# TMS320F28379D.net
KiCad netlist of a schematic drawn in Altium Designer
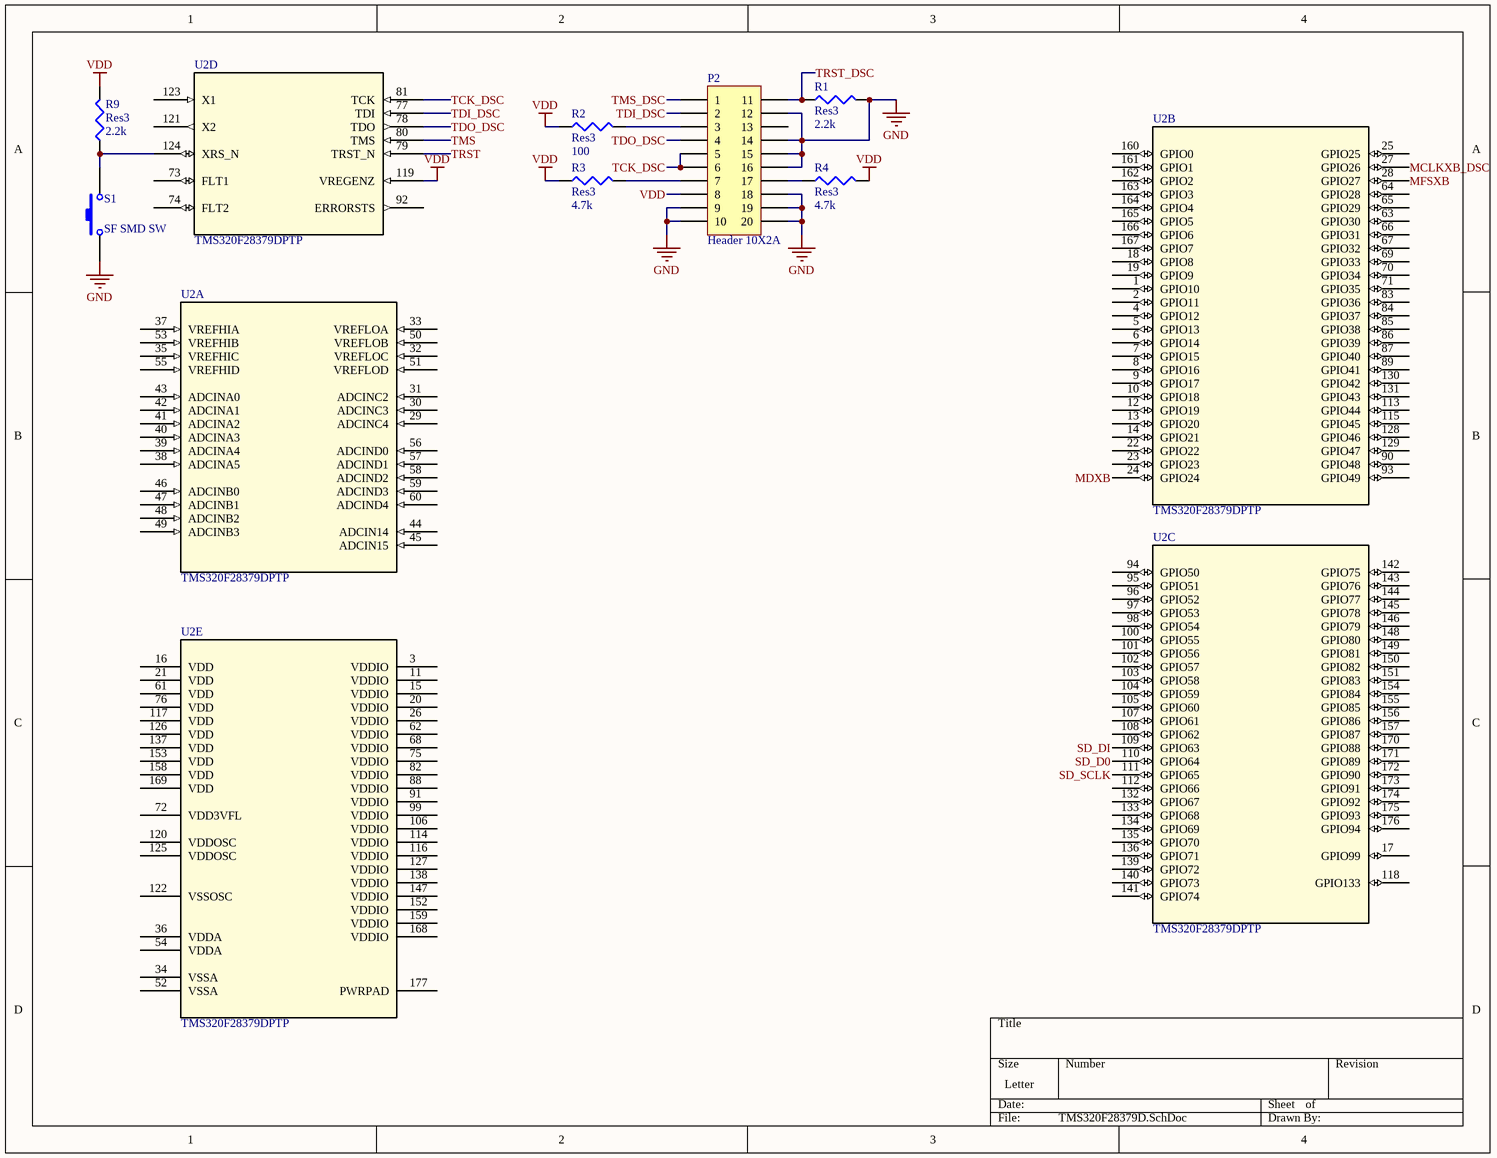
[diagram p0: TMS320F28379D.SchDoc]

(export (version "E")
  (design (tool "Eeschema 10.0.6"))
  (components
    (comp (ref "P2")
      (value "Header 10X2A")
      (footprint "HDR2X10_CEN")
      (description "Header, 10-Pin, Dual row")
      (fields (field (name "PUBLISHER") "Altium Limited"))
      (libsource (lib "Miscellaneous Connectors") (part "Header 10X2A"))
    )
    (comp (ref "R1")
      (value "Res3")
      (footprint "J1-0603")
      (description "Resistor")
      (fields (field (name "ALTIUM_VALUE") "2.2k") (field (name "PUBLISHER") "Altium Limited"))
      (libsource (lib "Miscellaneous Devices") (part "Res3"))
    )
    (comp (ref "R2")
      (value "Res3")
      (footprint "J1-0603")
      (description "Resistor")
      (fields (field (name "ALTIUM_VALUE") "100") (field (name "PUBLISHER") "Altium Limited"))
      (libsource (lib "Miscellaneous Devices") (part "Res3"))
    )
    (comp (ref "R3")
      (value "Res3")
      (footprint "J1-0603")
      (description "Resistor")
      (fields (field (name "ALTIUM_VALUE") "4.7k") (field (name "PUBLISHER") "Altium Limited"))
      (libsource (lib "Miscellaneous Devices") (part "Res3"))
    )
    (comp (ref "R4")
      (value "Res3")
      (footprint "J1-0603")
      (description "Resistor")
      (fields (field (name "ALTIUM_VALUE") "4.7k") (field (name "PUBLISHER") "Altium Limited"))
      (libsource (lib "Miscellaneous Devices") (part "Res3"))
    )
    (comp (ref "R9")
      (value "Res3")
      (footprint "J1-0603")
      (description "Resistor")
      (fields (field (name "ALTIUM_VALUE") "2.2k") (field (name "PUBLISHER") "Altium Limited"))
      (libsource (lib "Miscellaneous Devices") (part "Res3"))
    )
    (comp (ref "S1")
      (value "SF SMD SW")
      (footprint "SW_SMD")
      (description "DIGIKEY SW400-ND")
      (fields (field (name "PUBLISHER") "Altium Limited"))
      (libsource (lib "ECE LIB new") (part "SW-PB_1"))
    )
    (comp (ref "U2")
      (value "TMS320F28379DPTP")
      (footprint "PTP0176F_N")
      (description "Imported")
      (fields
        (field (name "PARTNUMBER") "TMS320F28379DPTPS")
        (field (name "MANUFACTURER") "Texas Instruments")
      )
      (libsource (lib "TMS320F28379DPTP") (part "TMS320F28379DPTP"))
    )
  )
  (nets
    (net (code "1") (name "/MCLKXB_DSC") (class "Default")
      (node (ref "U2") (pin "27") (pinfunction "GPIO26_27") (pintype "bidirectional"))
    )
    (net (code "2") (name "/MDXB") (class "Default")
      (node (ref "U2") (pin "24") (pinfunction "GPIO24_24") (pintype "bidirectional"))
    )
    (net (code "3") (name "/MFSXB") (class "Default")
      (node (ref "U2") (pin "28") (pinfunction "GPIO27_28") (pintype "bidirectional"))
    )
    (net (code "4") (name "/SD_D0") (class "Default")
      (node (ref "U2") (pin "110") (pinfunction "GPIO64_110") (pintype "bidirectional"))
    )
    (net (code "5") (name "/SD_DI") (class "Default")
      (node (ref "U2") (pin "109") (pinfunction "GPIO63_109") (pintype "bidirectional"))
    )
    (net (code "6") (name "/SD_SCLK") (class "Default")
      (node (ref "U2") (pin "111") (pinfunction "GPIO65_111") (pintype "bidirectional"))
    )
    (net (code "7") (name "/TCK_DSC") (class "Default")
      (node (ref "P2") (pin "5") (pinfunction "5_5") (pintype "passive"))
      (node (ref "P2") (pin "6") (pinfunction "6_6") (pintype "passive"))
      (node (ref "U2") (pin "81") (pinfunction "TCK_81") (pintype "input"))
    )
    (net (code "8") (name "/TDI_DSC") (class "Default")
      (node (ref "P2") (pin "2") (pinfunction "2_2") (pintype "passive"))
      (node (ref "U2") (pin "77") (pinfunction "TDI_77") (pintype "input"))
    )
    (net (code "9") (name "/TDO_DSC") (class "Default")
      (node (ref "P2") (pin "4") (pinfunction "4_4") (pintype "passive"))
      (node (ref "U2") (pin "78") (pinfunction "TDO_78") (pintype "output"))
    )
    (net (code "10") (name "/TMS") (class "Default")
      (node (ref "U2") (pin "80") (pinfunction "TMS_80") (pintype "input"))
    )
    (net (code "11") (name "/TMS_DSC") (class "Default")
      (node (ref "P2") (pin "1") (pinfunction "1_1") (pintype "passive"))
    )
    (net (code "12") (name "/TRST") (class "Default")
      (node (ref "U2") (pin "79") (pinfunction "TRST_N_79") (pintype "input"))
    )
    (net (code "13") (name "/TRST_DSC") (class "Default")
      (node (ref "P2") (pin "11") (pinfunction "11_11") (pintype "passive"))
      (node (ref "R1") (pin "1") (pinfunction "1_1") (pintype "passive"))
    )
    (net (code "14") (name "GND") (class "Default")
      (node (ref "P2") (pin "10") (pinfunction "10_10") (pintype "passive"))
      (node (ref "P2") (pin "12") (pinfunction "12_12") (pintype "passive"))
      (node (ref "P2") (pin "14") (pinfunction "14_14") (pintype "passive"))
      (node (ref "P2") (pin "15") (pinfunction "15_15") (pintype "passive"))
      (node (ref "P2") (pin "16") (pinfunction "16_16") (pintype "passive"))
      (node (ref "P2") (pin "18") (pinfunction "18_18") (pintype "passive"))
      (node (ref "P2") (pin "19") (pinfunction "19_19") (pintype "passive"))
      (node (ref "P2") (pin "20") (pinfunction "20_20") (pintype "passive"))
      (node (ref "P2") (pin "9") (pinfunction "9_9") (pintype "passive"))
      (node (ref "R1") (pin "2") (pinfunction "2_2") (pintype "passive"))
      (node (ref "S1") (pin "1") (pinfunction "1_1") (pintype "passive"))
    )
    (net (code "15") (name "Net-(P2-Pad3)") (class "Default")
      (node (ref "P2") (pin "3") (pinfunction "3_3") (pintype "passive"))
      (node (ref "R2") (pin "2") (pinfunction "2_2") (pintype "passive"))
    )
    (net (code "16") (name "Net-(P2-Pad7)") (class "Default")
      (node (ref "P2") (pin "7") (pinfunction "7_7") (pintype "passive"))
      (node (ref "R3") (pin "2") (pinfunction "2_2") (pintype "passive"))
    )
    (net (code "17") (name "Net-(P2-Pad17)") (class "Default")
      (node (ref "P2") (pin "17") (pinfunction "17_17") (pintype "passive"))
      (node (ref "R4") (pin "1") (pinfunction "1_1") (pintype "passive"))
    )
    (net (code "18") (name "Net-(U2D-XRS_N)") (class "Default")
      (node (ref "R9") (pin "1") (pinfunction "1_1") (pintype "passive"))
      (node (ref "S1") (pin "2") (pinfunction "2_2") (pintype "passive"))
      (node (ref "U2") (pin "124") (pinfunction "XRS_N_124") (pintype "bidirectional"))
    )
    (net (code "19") (name "VDD") (class "Default")
      (node (ref "P2") (pin "8") (pinfunction "8_8") (pintype "passive"))
      (node (ref "R2") (pin "1") (pinfunction "1_1") (pintype "passive"))
      (node (ref "R3") (pin "1") (pinfunction "1_1") (pintype "passive"))
      (node (ref "R4") (pin "2") (pinfunction "2_2") (pintype "passive"))
      (node (ref "R9") (pin "2") (pinfunction "2_2") (pintype "passive"))
      (node (ref "U2") (pin "119") (pinfunction "VREGENZ_119") (pintype "input"))
    )
    (net (code "20") (name "unconnected-(P2-Pad13)") (class "Default")
      (node (ref "P2") (pin "13") (pinfunction "13_13") (pintype "passive"))
    )
    (net (code "21") (name "unconnected-(U2A-ADCIN14-Pad44)") (class "Default")
      (node (ref "U2") (pin "44") (pinfunction "ADCIN14_44") (pintype "input"))
    )
    (net (code "22") (name "unconnected-(U2A-ADCIN15-Pad45)") (class "Default")
      (node (ref "U2") (pin "45") (pinfunction "ADCIN15_45") (pintype "input"))
    )
    (net (code "23") (name "unconnected-(U2A-ADCINA0-Pad43)") (class "Default")
      (node (ref "U2") (pin "43") (pinfunction "ADCINA0_43") (pintype "input"))
    )
    (net (code "24") (name "unconnected-(U2A-ADCINA1-Pad42)") (class "Default")
      (node (ref "U2") (pin "42") (pinfunction "ADCINA1_42") (pintype "input"))
    )
    (net (code "25") (name "unconnected-(U2A-ADCINA2-Pad41)") (class "Default")
      (node (ref "U2") (pin "41") (pinfunction "ADCINA2_41") (pintype "input"))
    )
    (net (code "26") (name "unconnected-(U2A-ADCINA3-Pad40)") (class "Default")
      (node (ref "U2") (pin "40") (pinfunction "ADCINA3_40") (pintype "input"))
    )
    (net (code "27") (name "unconnected-(U2A-ADCINA4-Pad39)") (class "Default")
      (node (ref "U2") (pin "39") (pinfunction "ADCINA4_39") (pintype "input"))
    )
    (net (code "28") (name "unconnected-(U2A-ADCINA5-Pad38)") (class "Default")
      (node (ref "U2") (pin "38") (pinfunction "ADCINA5_38") (pintype "input"))
    )
    (net (code "29") (name "unconnected-(U2A-ADCINB0-Pad46)") (class "Default")
      (node (ref "U2") (pin "46") (pinfunction "ADCINB0_46") (pintype "input"))
    )
    (net (code "30") (name "unconnected-(U2A-ADCINB1-Pad47)") (class "Default")
      (node (ref "U2") (pin "47") (pinfunction "ADCINB1_47") (pintype "input"))
    )
    (net (code "31") (name "unconnected-(U2A-ADCINB2-Pad48)") (class "Default")
      (node (ref "U2") (pin "48") (pinfunction "ADCINB2_48") (pintype "input"))
    )
    (net (code "32") (name "unconnected-(U2A-ADCINB3-Pad49)") (class "Default")
      (node (ref "U2") (pin "49") (pinfunction "ADCINB3_49") (pintype "input"))
    )
    (net (code "33") (name "unconnected-(U2A-ADCINC2-Pad31)") (class "Default")
      (node (ref "U2") (pin "31") (pinfunction "ADCINC2_31") (pintype "input"))
    )
    (net (code "34") (name "unconnected-(U2A-ADCINC3-Pad30)") (class "Default")
      (node (ref "U2") (pin "30") (pinfunction "ADCINC3_30") (pintype "input"))
    )
    (net (code "35") (name "unconnected-(U2A-ADCINC4-Pad29)") (class "Default")
      (node (ref "U2") (pin "29") (pinfunction "ADCINC4_29") (pintype "input"))
    )
    (net (code "36") (name "unconnected-(U2A-ADCIND0-Pad56)") (class "Default")
      (node (ref "U2") (pin "56") (pinfunction "ADCIND0_56") (pintype "input"))
    )
    (net (code "37") (name "unconnected-(U2A-ADCIND1-Pad57)") (class "Default")
      (node (ref "U2") (pin "57") (pinfunction "ADCIND1_57") (pintype "input"))
    )
    (net (code "38") (name "unconnected-(U2A-ADCIND2-Pad58)") (class "Default")
      (node (ref "U2") (pin "58") (pinfunction "ADCIND2_58") (pintype "input"))
    )
    (net (code "39") (name "unconnected-(U2A-ADCIND3-Pad59)") (class "Default")
      (node (ref "U2") (pin "59") (pinfunction "ADCIND3_59") (pintype "input"))
    )
    (net (code "40") (name "unconnected-(U2A-ADCIND4-Pad60)") (class "Default")
      (node (ref "U2") (pin "60") (pinfunction "ADCIND4_60") (pintype "input"))
    )
    (net (code "41") (name "unconnected-(U2A-VREFHIA-Pad37)") (class "Default")
      (node (ref "U2") (pin "37") (pinfunction "VREFHIA_37") (pintype "input"))
    )
    (net (code "42") (name "unconnected-(U2A-VREFHIB-Pad53)") (class "Default")
      (node (ref "U2") (pin "53") (pinfunction "VREFHIB_53") (pintype "input"))
    )
    (net (code "43") (name "unconnected-(U2A-VREFHIC-Pad35)") (class "Default")
      (node (ref "U2") (pin "35") (pinfunction "VREFHIC_35") (pintype "input"))
    )
    (net (code "44") (name "unconnected-(U2A-VREFHID-Pad55)") (class "Default")
      (node (ref "U2") (pin "55") (pinfunction "VREFHID_55") (pintype "input"))
    )
    (net (code "45") (name "unconnected-(U2A-VREFLOA-Pad33)") (class "Default")
      (node (ref "U2") (pin "33") (pinfunction "VREFLOA_33") (pintype "input"))
    )
    (net (code "46") (name "unconnected-(U2A-VREFLOB-Pad50)") (class "Default")
      (node (ref "U2") (pin "50") (pinfunction "VREFLOB_50") (pintype "input"))
    )
    (net (code "47") (name "unconnected-(U2A-VREFLOC-Pad32)") (class "Default")
      (node (ref "U2") (pin "32") (pinfunction "VREFLOC_32") (pintype "input"))
    )
    (net (code "48") (name "unconnected-(U2A-VREFLOD-Pad51)") (class "Default")
      (node (ref "U2") (pin "51") (pinfunction "VREFLOD_51") (pintype "input"))
    )
    (net (code "49") (name "unconnected-(U2B-GPIO0-Pad160)") (class "Default")
      (node (ref "U2") (pin "160") (pinfunction "GPIO0_160") (pintype "bidirectional"))
    )
    (net (code "50") (name "unconnected-(U2B-GPIO1-Pad161)") (class "Default")
      (node (ref "U2") (pin "161") (pinfunction "GPIO1_161") (pintype "bidirectional"))
    )
    (net (code "51") (name "unconnected-(U2B-GPIO2-Pad162)") (class "Default")
      (node (ref "U2") (pin "162") (pinfunction "GPIO2_162") (pintype "bidirectional"))
    )
    (net (code "52") (name "unconnected-(U2B-GPIO3-Pad163)") (class "Default")
      (node (ref "U2") (pin "163") (pinfunction "GPIO3_163") (pintype "bidirectional"))
    )
    (net (code "53") (name "unconnected-(U2B-GPIO4-Pad164)") (class "Default")
      (node (ref "U2") (pin "164") (pinfunction "GPIO4_164") (pintype "bidirectional"))
    )
    (net (code "54") (name "unconnected-(U2B-GPIO5-Pad165)") (class "Default")
      (node (ref "U2") (pin "165") (pinfunction "GPIO5_165") (pintype "bidirectional"))
    )
    (net (code "55") (name "unconnected-(U2B-GPIO6-Pad166)") (class "Default")
      (node (ref "U2") (pin "166") (pinfunction "GPIO6_166") (pintype "bidirectional"))
    )
    (net (code "56") (name "unconnected-(U2B-GPIO7-Pad167)") (class "Default")
      (node (ref "U2") (pin "167") (pinfunction "GPIO7_167") (pintype "bidirectional"))
    )
    (net (code "57") (name "unconnected-(U2B-GPIO8-Pad18)") (class "Default")
      (node (ref "U2") (pin "18") (pinfunction "GPIO8_18") (pintype "bidirectional"))
    )
    (net (code "58") (name "unconnected-(U2B-GPIO9-Pad19)") (class "Default")
      (node (ref "U2") (pin "19") (pinfunction "GPIO9_19") (pintype "bidirectional"))
    )
    (net (code "59") (name "unconnected-(U2B-GPIO10-Pad1)") (class "Default")
      (node (ref "U2") (pin "1") (pinfunction "GPIO10_1") (pintype "bidirectional"))
    )
    (net (code "60") (name "unconnected-(U2B-GPIO11-Pad2)") (class "Default")
      (node (ref "U2") (pin "2") (pinfunction "GPIO11_2") (pintype "bidirectional"))
    )
    (net (code "61") (name "unconnected-(U2B-GPIO12-Pad4)") (class "Default")
      (node (ref "U2") (pin "4") (pinfunction "GPIO12_4") (pintype "bidirectional"))
    )
    (net (code "62") (name "unconnected-(U2B-GPIO13-Pad5)") (class "Default")
      (node (ref "U2") (pin "5") (pinfunction "GPIO13_5") (pintype "bidirectional"))
    )
    (net (code "63") (name "unconnected-(U2B-GPIO14-Pad6)") (class "Default")
      (node (ref "U2") (pin "6") (pinfunction "GPIO14_6") (pintype "bidirectional"))
    )
    (net (code "64") (name "unconnected-(U2B-GPIO15-Pad7)") (class "Default")
      (node (ref "U2") (pin "7") (pinfunction "GPIO15_7") (pintype "bidirectional"))
    )
    (net (code "65") (name "unconnected-(U2B-GPIO16-Pad8)") (class "Default")
      (node (ref "U2") (pin "8") (pinfunction "GPIO16_8") (pintype "bidirectional"))
    )
    (net (code "66") (name "unconnected-(U2B-GPIO17-Pad9)") (class "Default")
      (node (ref "U2") (pin "9") (pinfunction "GPIO17_9") (pintype "bidirectional"))
    )
    (net (code "67") (name "unconnected-(U2B-GPIO18-Pad10)") (class "Default")
      (node (ref "U2") (pin "10") (pinfunction "GPIO18_10") (pintype "bidirectional"))
    )
    (net (code "68") (name "unconnected-(U2B-GPIO19-Pad12)") (class "Default")
      (node (ref "U2") (pin "12") (pinfunction "GPIO19_12") (pintype "bidirectional"))
    )
    (net (code "69") (name "unconnected-(U2B-GPIO20-Pad13)") (class "Default")
      (node (ref "U2") (pin "13") (pinfunction "GPIO20_13") (pintype "bidirectional"))
    )
    (net (code "70") (name "unconnected-(U2B-GPIO21-Pad14)") (class "Default")
      (node (ref "U2") (pin "14") (pinfunction "GPIO21_14") (pintype "bidirectional"))
    )
    (net (code "71") (name "unconnected-(U2B-GPIO22-Pad22)") (class "Default")
      (node (ref "U2") (pin "22") (pinfunction "GPIO22_22") (pintype "bidirectional"))
    )
    (net (code "72") (name "unconnected-(U2B-GPIO23-Pad23)") (class "Default")
      (node (ref "U2") (pin "23") (pinfunction "GPIO23_23") (pintype "bidirectional"))
    )
    (net (code "73") (name "unconnected-(U2B-GPIO25-Pad25)") (class "Default")
      (node (ref "U2") (pin "25") (pinfunction "GPIO25_25") (pintype "bidirectional"))
    )
    (net (code "74") (name "unconnected-(U2B-GPIO28-Pad64)") (class "Default")
      (node (ref "U2") (pin "64") (pinfunction "GPIO28_64") (pintype "bidirectional"))
    )
    (net (code "75") (name "unconnected-(U2B-GPIO29-Pad65)") (class "Default")
      (node (ref "U2") (pin "65") (pinfunction "GPIO29_65") (pintype "bidirectional"))
    )
    (net (code "76") (name "unconnected-(U2B-GPIO30-Pad63)") (class "Default")
      (node (ref "U2") (pin "63") (pinfunction "GPIO30_63") (pintype "bidirectional"))
    )
    (net (code "77") (name "unconnected-(U2B-GPIO31-Pad66)") (class "Default")
      (node (ref "U2") (pin "66") (pinfunction "GPIO31_66") (pintype "bidirectional"))
    )
    (net (code "78") (name "unconnected-(U2B-GPIO32-Pad67)") (class "Default")
      (node (ref "U2") (pin "67") (pinfunction "GPIO32_67") (pintype "bidirectional"))
    )
    (net (code "79") (name "unconnected-(U2B-GPIO33-Pad69)") (class "Default")
      (node (ref "U2") (pin "69") (pinfunction "GPIO33_69") (pintype "bidirectional"))
    )
    (net (code "80") (name "unconnected-(U2B-GPIO34-Pad70)") (class "Default")
      (node (ref "U2") (pin "70") (pinfunction "GPIO34_70") (pintype "bidirectional"))
    )
    (net (code "81") (name "unconnected-(U2B-GPIO35-Pad71)") (class "Default")
      (node (ref "U2") (pin "71") (pinfunction "GPIO35_71") (pintype "bidirectional"))
    )
    (net (code "82") (name "unconnected-(U2B-GPIO36-Pad83)") (class "Default")
      (node (ref "U2") (pin "83") (pinfunction "GPIO36_83") (pintype "bidirectional"))
    )
    (net (code "83") (name "unconnected-(U2B-GPIO37-Pad84)") (class "Default")
      (node (ref "U2") (pin "84") (pinfunction "GPIO37_84") (pintype "bidirectional"))
    )
    (net (code "84") (name "unconnected-(U2B-GPIO38-Pad85)") (class "Default")
      (node (ref "U2") (pin "85") (pinfunction "GPIO38_85") (pintype "bidirectional"))
    )
    (net (code "85") (name "unconnected-(U2B-GPIO39-Pad86)") (class "Default")
      (node (ref "U2") (pin "86") (pinfunction "GPIO39_86") (pintype "bidirectional"))
    )
    (net (code "86") (name "unconnected-(U2B-GPIO40-Pad87)") (class "Default")
      (node (ref "U2") (pin "87") (pinfunction "GPIO40_87") (pintype "bidirectional"))
    )
    (net (code "87") (name "unconnected-(U2B-GPIO41-Pad89)") (class "Default")
      (node (ref "U2") (pin "89") (pinfunction "GPIO41_89") (pintype "bidirectional"))
    )
    (net (code "88") (name "unconnected-(U2B-GPIO42-Pad130)") (class "Default")
      (node (ref "U2") (pin "130") (pinfunction "GPIO42_130") (pintype "bidirectional"))
    )
    (net (code "89") (name "unconnected-(U2B-GPIO43-Pad131)") (class "Default")
      (node (ref "U2") (pin "131") (pinfunction "GPIO43_131") (pintype "bidirectional"))
    )
    (net (code "90") (name "unconnected-(U2B-GPIO44-Pad113)") (class "Default")
      (node (ref "U2") (pin "113") (pinfunction "GPIO44_113") (pintype "bidirectional"))
    )
    (net (code "91") (name "unconnected-(U2B-GPIO45-Pad115)") (class "Default")
      (node (ref "U2") (pin "115") (pinfunction "GPIO45_115") (pintype "bidirectional"))
    )
    (net (code "92") (name "unconnected-(U2B-GPIO46-Pad128)") (class "Default")
      (node (ref "U2") (pin "128") (pinfunction "GPIO46_128") (pintype "bidirectional"))
    )
    (net (code "93") (name "unconnected-(U2B-GPIO47-Pad129)") (class "Default")
      (node (ref "U2") (pin "129") (pinfunction "GPIO47_129") (pintype "bidirectional"))
    )
    (net (code "94") (name "unconnected-(U2B-GPIO48-Pad90)") (class "Default")
      (node (ref "U2") (pin "90") (pinfunction "GPIO48_90") (pintype "bidirectional"))
    )
    (net (code "95") (name "unconnected-(U2B-GPIO49-Pad93)") (class "Default")
      (node (ref "U2") (pin "93") (pinfunction "GPIO49_93") (pintype "bidirectional"))
    )
    (net (code "96") (name "unconnected-(U2C-GPIO50-Pad94)") (class "Default")
      (node (ref "U2") (pin "94") (pinfunction "GPIO50_94") (pintype "bidirectional"))
    )
    (net (code "97") (name "unconnected-(U2C-GPIO51-Pad95)") (class "Default")
      (node (ref "U2") (pin "95") (pinfunction "GPIO51_95") (pintype "bidirectional"))
    )
    (net (code "98") (name "unconnected-(U2C-GPIO52-Pad96)") (class "Default")
      (node (ref "U2") (pin "96") (pinfunction "GPIO52_96") (pintype "bidirectional"))
    )
    (net (code "99") (name "unconnected-(U2C-GPIO53-Pad97)") (class "Default")
      (node (ref "U2") (pin "97") (pinfunction "GPIO53_97") (pintype "bidirectional"))
    )
    (net (code "100") (name "unconnected-(U2C-GPIO54-Pad98)") (class "Default")
      (node (ref "U2") (pin "98") (pinfunction "GPIO54_98") (pintype "bidirectional"))
    )
    (net (code "101") (name "unconnected-(U2C-GPIO55-Pad100)") (class "Default")
      (node (ref "U2") (pin "100") (pinfunction "GPIO55_100") (pintype "bidirectional"))
    )
    (net (code "102") (name "unconnected-(U2C-GPIO56-Pad101)") (class "Default")
      (node (ref "U2") (pin "101") (pinfunction "GPIO56_101") (pintype "bidirectional"))
    )
    (net (code "103") (name "unconnected-(U2C-GPIO57-Pad102)") (class "Default")
      (node (ref "U2") (pin "102") (pinfunction "GPIO57_102") (pintype "bidirectional"))
    )
    (net (code "104") (name "unconnected-(U2C-GPIO58-Pad103)") (class "Default")
      (node (ref "U2") (pin "103") (pinfunction "GPIO58_103") (pintype "bidirectional"))
    )
    (net (code "105") (name "unconnected-(U2C-GPIO59-Pad104)") (class "Default")
      (node (ref "U2") (pin "104") (pinfunction "GPIO59_104") (pintype "bidirectional"))
    )
    (net (code "106") (name "unconnected-(U2C-GPIO60-Pad105)") (class "Default")
      (node (ref "U2") (pin "105") (pinfunction "GPIO60_105") (pintype "bidirectional"))
    )
    (net (code "107") (name "unconnected-(U2C-GPIO61-Pad107)") (class "Default")
      (node (ref "U2") (pin "107") (pinfunction "GPIO61_107") (pintype "bidirectional"))
    )
    (net (code "108") (name "unconnected-(U2C-GPIO62-Pad108)") (class "Default")
      (node (ref "U2") (pin "108") (pinfunction "GPIO62_108") (pintype "bidirectional"))
    )
    (net (code "109") (name "unconnected-(U2C-GPIO66-Pad112)") (class "Default")
      (node (ref "U2") (pin "112") (pinfunction "GPIO66_112") (pintype "bidirectional"))
    )
    (net (code "110") (name "unconnected-(U2C-GPIO67-Pad132)") (class "Default")
      (node (ref "U2") (pin "132") (pinfunction "GPIO67_132") (pintype "bidirectional"))
    )
    (net (code "111") (name "unconnected-(U2C-GPIO68-Pad133)") (class "Default")
      (node (ref "U2") (pin "133") (pinfunction "GPIO68_133") (pintype "bidirectional"))
    )
    (net (code "112") (name "unconnected-(U2C-GPIO69-Pad134)") (class "Default")
      (node (ref "U2") (pin "134") (pinfunction "GPIO69_134") (pintype "bidirectional"))
    )
    (net (code "113") (name "unconnected-(U2C-GPIO70-Pad135)") (class "Default")
      (node (ref "U2") (pin "135") (pinfunction "GPIO70_135") (pintype "bidirectional"))
    )
    (net (code "114") (name "unconnected-(U2C-GPIO71-Pad136)") (class "Default")
      (node (ref "U2") (pin "136") (pinfunction "GPIO71_136") (pintype "bidirectional"))
    )
    (net (code "115") (name "unconnected-(U2C-GPIO72-Pad139)") (class "Default")
      (node (ref "U2") (pin "139") (pinfunction "GPIO72_139") (pintype "bidirectional"))
    )
    (net (code "116") (name "unconnected-(U2C-GPIO73-Pad140)") (class "Default")
      (node (ref "U2") (pin "140") (pinfunction "GPIO73_140") (pintype "bidirectional"))
    )
    (net (code "117") (name "unconnected-(U2C-GPIO74-Pad141)") (class "Default")
      (node (ref "U2") (pin "141") (pinfunction "GPIO74_141") (pintype "bidirectional"))
    )
    (net (code "118") (name "unconnected-(U2C-GPIO75-Pad142)") (class "Default")
      (node (ref "U2") (pin "142") (pinfunction "GPIO75_142") (pintype "bidirectional"))
    )
    (net (code "119") (name "unconnected-(U2C-GPIO76-Pad143)") (class "Default")
      (node (ref "U2") (pin "143") (pinfunction "GPIO76_143") (pintype "bidirectional"))
    )
    (net (code "120") (name "unconnected-(U2C-GPIO77-Pad144)") (class "Default")
      (node (ref "U2") (pin "144") (pinfunction "GPIO77_144") (pintype "bidirectional"))
    )
    (net (code "121") (name "unconnected-(U2C-GPIO78-Pad145)") (class "Default")
      (node (ref "U2") (pin "145") (pinfunction "GPIO78_145") (pintype "bidirectional"))
    )
    (net (code "122") (name "unconnected-(U2C-GPIO79-Pad146)") (class "Default")
      (node (ref "U2") (pin "146") (pinfunction "GPIO79_146") (pintype "bidirectional"))
    )
    (net (code "123") (name "unconnected-(U2C-GPIO80-Pad148)") (class "Default")
      (node (ref "U2") (pin "148") (pinfunction "GPIO80_148") (pintype "bidirectional"))
    )
    (net (code "124") (name "unconnected-(U2C-GPIO81-Pad149)") (class "Default")
      (node (ref "U2") (pin "149") (pinfunction "GPIO81_149") (pintype "bidirectional"))
    )
    (net (code "125") (name "unconnected-(U2C-GPIO82-Pad150)") (class "Default")
      (node (ref "U2") (pin "150") (pinfunction "GPIO82_150") (pintype "bidirectional"))
    )
    (net (code "126") (name "unconnected-(U2C-GPIO83-Pad151)") (class "Default")
      (node (ref "U2") (pin "151") (pinfunction "GPIO83_151") (pintype "bidirectional"))
    )
    (net (code "127") (name "unconnected-(U2C-GPIO84-Pad154)") (class "Default")
      (node (ref "U2") (pin "154") (pinfunction "GPIO84_154") (pintype "bidirectional"))
    )
    (net (code "128") (name "unconnected-(U2C-GPIO85-Pad155)") (class "Default")
      (node (ref "U2") (pin "155") (pinfunction "GPIO85_155") (pintype "bidirectional"))
    )
    (net (code "129") (name "unconnected-(U2C-GPIO86-Pad156)") (class "Default")
      (node (ref "U2") (pin "156") (pinfunction "GPIO86_156") (pintype "bidirectional"))
    )
    (net (code "130") (name "unconnected-(U2C-GPIO87-Pad157)") (class "Default")
      (node (ref "U2") (pin "157") (pinfunction "GPIO87_157") (pintype "bidirectional"))
    )
    (net (code "131") (name "unconnected-(U2C-GPIO88-Pad170)") (class "Default")
      (node (ref "U2") (pin "170") (pinfunction "GPIO88_170") (pintype "bidirectional"))
    )
    (net (code "132") (name "unconnected-(U2C-GPIO89-Pad171)") (class "Default")
      (node (ref "U2") (pin "171") (pinfunction "GPIO89_171") (pintype "bidirectional"))
    )
    (net (code "133") (name "unconnected-(U2C-GPIO90-Pad172)") (class "Default")
      (node (ref "U2") (pin "172") (pinfunction "GPIO90_172") (pintype "bidirectional"))
    )
    (net (code "134") (name "unconnected-(U2C-GPIO91-Pad173)") (class "Default")
      (node (ref "U2") (pin "173") (pinfunction "GPIO91_173") (pintype "bidirectional"))
    )
    (net (code "135") (name "unconnected-(U2C-GPIO92-Pad174)") (class "Default")
      (node (ref "U2") (pin "174") (pinfunction "GPIO92_174") (pintype "bidirectional"))
    )
    (net (code "136") (name "unconnected-(U2C-GPIO93-Pad175)") (class "Default")
      (node (ref "U2") (pin "175") (pinfunction "GPIO93_175") (pintype "bidirectional"))
    )
    (net (code "137") (name "unconnected-(U2C-GPIO94-Pad176)") (class "Default")
      (node (ref "U2") (pin "176") (pinfunction "GPIO94_176") (pintype "bidirectional"))
    )
    (net (code "138") (name "unconnected-(U2C-GPIO99-Pad17)") (class "Default")
      (node (ref "U2") (pin "17") (pinfunction "GPIO99_17") (pintype "bidirectional"))
    )
    (net (code "139") (name "unconnected-(U2C-GPIO133-Pad118)") (class "Default")
      (node (ref "U2") (pin "118") (pinfunction "GPIO133_118") (pintype "bidirectional"))
    )
    (net (code "140") (name "unconnected-(U2D-ERRORSTS-Pad92)") (class "Default")
      (node (ref "U2") (pin "92") (pinfunction "ERRORSTS_92") (pintype "output"))
    )
    (net (code "141") (name "unconnected-(U2D-FLT1-Pad73)") (class "Default")
      (node (ref "U2") (pin "73") (pinfunction "FLT1_73") (pintype "bidirectional"))
    )
    (net (code "142") (name "unconnected-(U2D-FLT2-Pad74)") (class "Default")
      (node (ref "U2") (pin "74") (pinfunction "FLT2_74") (pintype "bidirectional"))
    )
    (net (code "143") (name "unconnected-(U2D-X1-Pad123)") (class "Default")
      (node (ref "U2") (pin "123") (pinfunction "X1_123") (pintype "input"))
    )
    (net (code "144") (name "unconnected-(U2D-X2-Pad121)") (class "Default")
      (node (ref "U2") (pin "121") (pinfunction "X2_121") (pintype "output"))
    )
    (net (code "145") (name "unconnected-(U2E-PWRPAD-Pad177)") (class "Default")
      (node (ref "U2") (pin "177") (pinfunction "PWRPAD_177") (pintype "power_in"))
    )
    (net (code "146") (name "unconnected-(U2E-VDD-Pad16)") (class "Default")
      (node (ref "U2") (pin "16") (pinfunction "VDD_16") (pintype "power_in"))
    )
    (net (code "147") (name "unconnected-(U2E-VDD-Pad21)") (class "Default")
      (node (ref "U2") (pin "21") (pinfunction "VDD_21") (pintype "power_in"))
    )
    (net (code "148") (name "unconnected-(U2E-VDD-Pad61)") (class "Default")
      (node (ref "U2") (pin "61") (pinfunction "VDD_61") (pintype "power_in"))
    )
    (net (code "149") (name "unconnected-(U2E-VDD-Pad76)") (class "Default")
      (node (ref "U2") (pin "76") (pinfunction "VDD_76") (pintype "power_in"))
    )
    (net (code "150") (name "unconnected-(U2E-VDD-Pad117)") (class "Default")
      (node (ref "U2") (pin "117") (pinfunction "VDD_117") (pintype "power_in"))
    )
    (net (code "151") (name "unconnected-(U2E-VDD-Pad126)") (class "Default")
      (node (ref "U2") (pin "126") (pinfunction "VDD_126") (pintype "power_in"))
    )
    (net (code "152") (name "unconnected-(U2E-VDD-Pad137)") (class "Default")
      (node (ref "U2") (pin "137") (pinfunction "VDD_137") (pintype "power_in"))
    )
    (net (code "153") (name "unconnected-(U2E-VDD-Pad153)") (class "Default")
      (node (ref "U2") (pin "153") (pinfunction "VDD_153") (pintype "power_in"))
    )
    (net (code "154") (name "unconnected-(U2E-VDD-Pad158)") (class "Default")
      (node (ref "U2") (pin "158") (pinfunction "VDD_158") (pintype "power_in"))
    )
    (net (code "155") (name "unconnected-(U2E-VDD-Pad169)") (class "Default")
      (node (ref "U2") (pin "169") (pinfunction "VDD_169") (pintype "power_in"))
    )
    (net (code "156") (name "unconnected-(U2E-VDD3VFL-Pad72)") (class "Default")
      (node (ref "U2") (pin "72") (pinfunction "VDD3VFL_72") (pintype "power_in"))
    )
    (net (code "157") (name "unconnected-(U2E-VDDA-Pad36)") (class "Default")
      (node (ref "U2") (pin "36") (pinfunction "VDDA_36") (pintype "power_in"))
    )
    (net (code "158") (name "unconnected-(U2E-VDDA-Pad54)") (class "Default")
      (node (ref "U2") (pin "54") (pinfunction "VDDA_54") (pintype "power_in"))
    )
    (net (code "159") (name "unconnected-(U2E-VDDIO-Pad3)") (class "Default")
      (node (ref "U2") (pin "3") (pinfunction "VDDIO_3") (pintype "power_in"))
    )
    (net (code "160") (name "unconnected-(U2E-VDDIO-Pad11)") (class "Default")
      (node (ref "U2") (pin "11") (pinfunction "VDDIO_11") (pintype "power_in"))
    )
    (net (code "161") (name "unconnected-(U2E-VDDIO-Pad15)") (class "Default")
      (node (ref "U2") (pin "15") (pinfunction "VDDIO_15") (pintype "power_in"))
    )
    (net (code "162") (name "unconnected-(U2E-VDDIO-Pad20)") (class "Default")
      (node (ref "U2") (pin "20") (pinfunction "VDDIO_20") (pintype "power_in"))
    )
    (net (code "163") (name "unconnected-(U2E-VDDIO-Pad26)") (class "Default")
      (node (ref "U2") (pin "26") (pinfunction "VDDIO_26") (pintype "power_in"))
    )
    (net (code "164") (name "unconnected-(U2E-VDDIO-Pad62)") (class "Default")
      (node (ref "U2") (pin "62") (pinfunction "VDDIO_62") (pintype "power_in"))
    )
    (net (code "165") (name "unconnected-(U2E-VDDIO-Pad68)") (class "Default")
      (node (ref "U2") (pin "68") (pinfunction "VDDIO_68") (pintype "power_in"))
    )
    (net (code "166") (name "unconnected-(U2E-VDDIO-Pad75)") (class "Default")
      (node (ref "U2") (pin "75") (pinfunction "VDDIO_75") (pintype "power_in"))
    )
    (net (code "167") (name "unconnected-(U2E-VDDIO-Pad82)") (class "Default")
      (node (ref "U2") (pin "82") (pinfunction "VDDIO_82") (pintype "power_in"))
    )
    (net (code "168") (name "unconnected-(U2E-VDDIO-Pad88)") (class "Default")
      (node (ref "U2") (pin "88") (pinfunction "VDDIO_88") (pintype "power_in"))
    )
    (net (code "169") (name "unconnected-(U2E-VDDIO-Pad91)") (class "Default")
      (node (ref "U2") (pin "91") (pinfunction "VDDIO_91") (pintype "power_in"))
    )
    (net (code "170") (name "unconnected-(U2E-VDDIO-Pad99)") (class "Default")
      (node (ref "U2") (pin "99") (pinfunction "VDDIO_99") (pintype "power_in"))
    )
    (net (code "171") (name "unconnected-(U2E-VDDIO-Pad106)") (class "Default")
      (node (ref "U2") (pin "106") (pinfunction "VDDIO_106") (pintype "power_in"))
    )
    (net (code "172") (name "unconnected-(U2E-VDDIO-Pad114)") (class "Default")
      (node (ref "U2") (pin "114") (pinfunction "VDDIO_114") (pintype "power_in"))
    )
    (net (code "173") (name "unconnected-(U2E-VDDIO-Pad116)") (class "Default")
      (node (ref "U2") (pin "116") (pinfunction "VDDIO_116") (pintype "power_in"))
    )
    (net (code "174") (name "unconnected-(U2E-VDDIO-Pad127)") (class "Default")
      (node (ref "U2") (pin "127") (pinfunction "VDDIO_127") (pintype "power_in"))
    )
    (net (code "175") (name "unconnected-(U2E-VDDIO-Pad138)") (class "Default")
      (node (ref "U2") (pin "138") (pinfunction "VDDIO_138") (pintype "power_in"))
    )
    (net (code "176") (name "unconnected-(U2E-VDDIO-Pad147)") (class "Default")
      (node (ref "U2") (pin "147") (pinfunction "VDDIO_147") (pintype "power_in"))
    )
    (net (code "177") (name "unconnected-(U2E-VDDIO-Pad152)") (class "Default")
      (node (ref "U2") (pin "152") (pinfunction "VDDIO_152") (pintype "power_in"))
    )
    (net (code "178") (name "unconnected-(U2E-VDDIO-Pad159)") (class "Default")
      (node (ref "U2") (pin "159") (pinfunction "VDDIO_159") (pintype "power_in"))
    )
    (net (code "179") (name "unconnected-(U2E-VDDIO-Pad168)") (class "Default")
      (node (ref "U2") (pin "168") (pinfunction "VDDIO_168") (pintype "power_in"))
    )
    (net (code "180") (name "unconnected-(U2E-VDDOSC-Pad120)") (class "Default")
      (node (ref "U2") (pin "120") (pinfunction "VDDOSC_120") (pintype "power_in"))
    )
    (net (code "181") (name "unconnected-(U2E-VDDOSC-Pad125)") (class "Default")
      (node (ref "U2") (pin "125") (pinfunction "VDDOSC_125") (pintype "power_in"))
    )
    (net (code "182") (name "unconnected-(U2E-VSSA-Pad34)") (class "Default")
      (node (ref "U2") (pin "34") (pinfunction "VSSA_34") (pintype "power_in"))
    )
    (net (code "183") (name "unconnected-(U2E-VSSA-Pad52)") (class "Default")
      (node (ref "U2") (pin "52") (pinfunction "VSSA_52") (pintype "power_in"))
    )
    (net (code "184") (name "unconnected-(U2E-VSSOSC-Pad122)") (class "Default")
      (node (ref "U2") (pin "122") (pinfunction "VSSOSC_122") (pintype "power_in"))
    )
  )
)
